# schematic.net
KiCad netlist of a schematic drawn in EAGLE
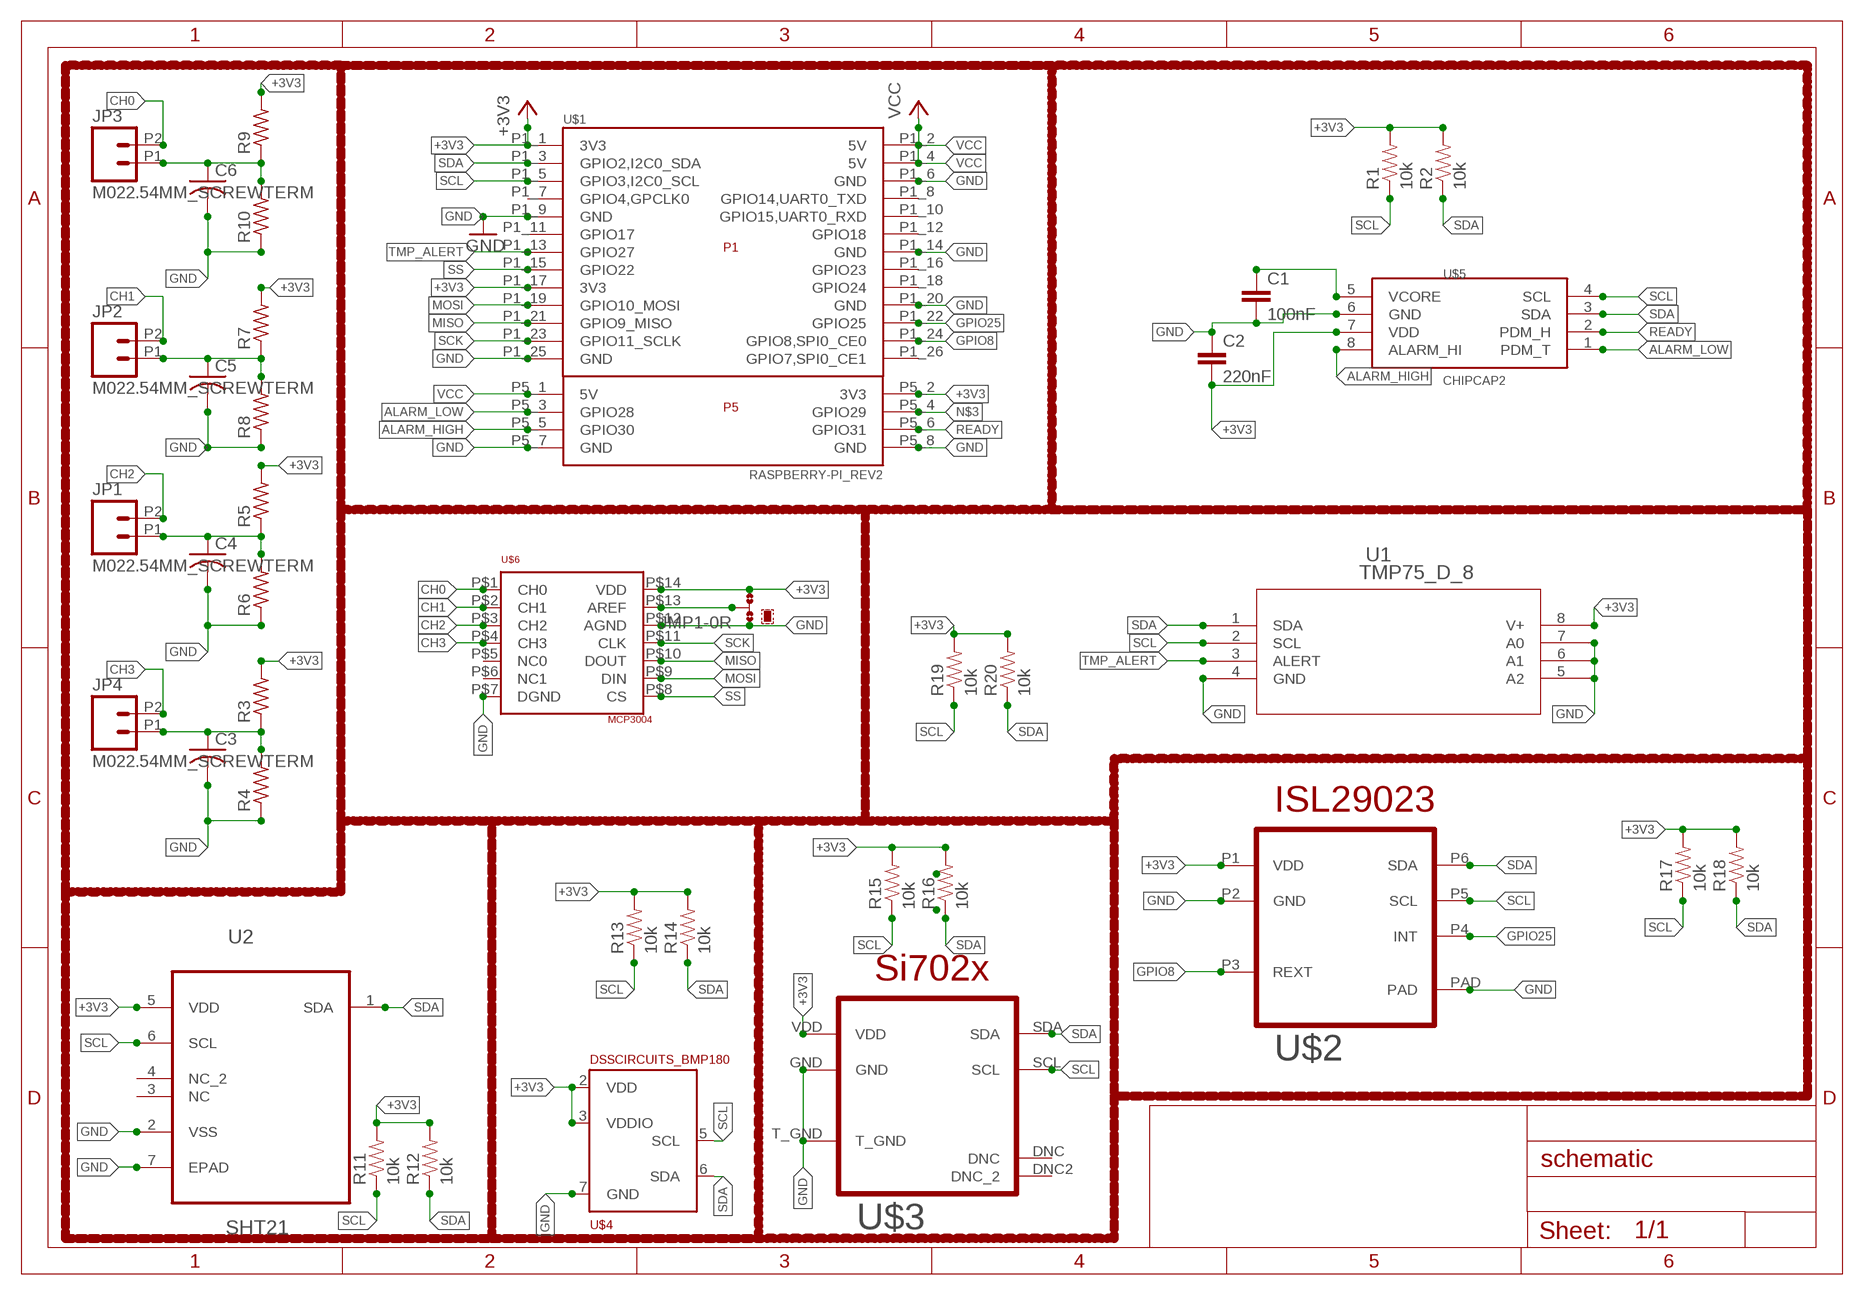
[diagram p0: schematic, sheet 1]

(export (version "E")
  (design (tool "Eeschema 10.0.6"))
  (components
    (comp (ref "C1")
      (value "100nF")
      (footprint "eagle-import:0402-CAP")
      (libsource (lib "eagle-import") (part "CAP0402-CAP"))
    )
    (comp (ref "C2")
      (value "220nF")
      (footprint "eagle-import:0402-CAP")
      (libsource (lib "eagle-import") (part "CAP0402-CAP"))
    )
    (comp (ref "C3")
      (value "C-USC0402")
      (footprint "eagle-import:C0402")
      (libsource (lib "eagle-import") (part "C-USC0402"))
    )
    (comp (ref "C4")
      (value "C-USC0402")
      (footprint "eagle-import:C0402")
      (libsource (lib "eagle-import") (part "C-USC0402"))
    )
    (comp (ref "C5")
      (value "C-USC0402")
      (footprint "eagle-import:C0402")
      (libsource (lib "eagle-import") (part "C-USC0402"))
    )
    (comp (ref "C6")
      (value "C-USC0402")
      (footprint "eagle-import:C0402")
      (libsource (lib "eagle-import") (part "C-USC0402"))
    )
    (comp (ref "JMP1")
      (value "0R-JUMPA")
      (footprint "eagle-import:A0R-JMP")
      (libsource (lib "eagle-import") (part "0R-JUMPA"))
    )
    (comp (ref "JP1")
      (value "M022.54MM_SCREWTERM")
      (footprint "eagle-import:1X02_2.54_SCREWTERM")
      (libsource (lib "eagle-import") (part "M022.54MM_SCREWTERM"))
    )
    (comp (ref "JP2")
      (value "M022.54MM_SCREWTERM")
      (footprint "eagle-import:1X02_2.54_SCREWTERM")
      (libsource (lib "eagle-import") (part "M022.54MM_SCREWTERM"))
    )
    (comp (ref "JP3")
      (value "M022.54MM_SCREWTERM")
      (footprint "eagle-import:1X02_2.54_SCREWTERM")
      (libsource (lib "eagle-import") (part "M022.54MM_SCREWTERM"))
    )
    (comp (ref "JP4")
      (value "M022.54MM_SCREWTERM")
      (footprint "eagle-import:1X02_2.54_SCREWTERM")
      (libsource (lib "eagle-import") (part "M022.54MM_SCREWTERM"))
    )
    (comp (ref "R1")
      (value "10k")
      (footprint "eagle-import:0603-RES")
      (libsource (lib "eagle-import") (part "RESISTOR0603"))
    )
    (comp (ref "R2")
      (value "10k")
      (footprint "eagle-import:0603-RES")
      (libsource (lib "eagle-import") (part "RESISTOR0603"))
    )
    (comp (ref "R3")
      (value "R-US_R0402")
      (footprint "eagle-import:R0402")
      (libsource (lib "eagle-import") (part "R-US_R0402"))
    )
    (comp (ref "R4")
      (value "R-US_R0402")
      (footprint "eagle-import:R0402")
      (libsource (lib "eagle-import") (part "R-US_R0402"))
    )
    (comp (ref "R5")
      (value "R-US_R0402")
      (footprint "eagle-import:R0402")
      (libsource (lib "eagle-import") (part "R-US_R0402"))
    )
    (comp (ref "R6")
      (value "R-US_R0402")
      (footprint "eagle-import:R0402")
      (libsource (lib "eagle-import") (part "R-US_R0402"))
    )
    (comp (ref "R7")
      (value "R-US_R0402")
      (footprint "eagle-import:R0402")
      (libsource (lib "eagle-import") (part "R-US_R0402"))
    )
    (comp (ref "R8")
      (value "R-US_R0402")
      (footprint "eagle-import:R0402")
      (libsource (lib "eagle-import") (part "R-US_R0402"))
    )
    (comp (ref "R9")
      (value "R-US_R0402")
      (footprint "eagle-import:R0402")
      (libsource (lib "eagle-import") (part "R-US_R0402"))
    )
    (comp (ref "R10")
      (value "R-US_R0402")
      (footprint "eagle-import:R0402")
      (libsource (lib "eagle-import") (part "R-US_R0402"))
    )
    (comp (ref "R11")
      (value "10k")
      (footprint "eagle-import:0603-RES")
      (libsource (lib "eagle-import") (part "RESISTOR0603"))
    )
    (comp (ref "R12")
      (value "10k")
      (footprint "eagle-import:0603-RES")
      (libsource (lib "eagle-import") (part "RESISTOR0603"))
    )
    (comp (ref "R13")
      (value "10k")
      (footprint "eagle-import:0603-RES")
      (libsource (lib "eagle-import") (part "RESISTOR0603"))
    )
    (comp (ref "R14")
      (value "10k")
      (footprint "eagle-import:0603-RES")
      (libsource (lib "eagle-import") (part "RESISTOR0603"))
    )
    (comp (ref "R15")
      (value "10k")
      (footprint "eagle-import:0603-RES")
      (libsource (lib "eagle-import") (part "RESISTOR0603"))
    )
    (comp (ref "R16")
      (value "10k")
      (footprint "eagle-import:0603-RES")
      (libsource (lib "eagle-import") (part "RESISTOR0603"))
    )
    (comp (ref "R17")
      (value "10k")
      (footprint "eagle-import:0603-RES")
      (libsource (lib "eagle-import") (part "RESISTOR0603"))
    )
    (comp (ref "R18")
      (value "10k")
      (footprint "eagle-import:0603-RES")
      (libsource (lib "eagle-import") (part "RESISTOR0603"))
    )
    (comp (ref "R19")
      (value "10k")
      (footprint "eagle-import:0603-RES")
      (libsource (lib "eagle-import") (part "RESISTOR0603"))
    )
    (comp (ref "R20")
      (value "10k")
      (footprint "eagle-import:0603-RES")
      (libsource (lib "eagle-import") (part "RESISTOR0603"))
    )
    (comp (ref "U$1")
      (value "RASPBERRY-PI_REV2")
      (footprint "eagle-import:RASPBERRY-PI_REV2")
      (libsource (lib "eagle-import") (part "RASPBERRY-PI_REV2"))
    )
    (comp (ref "U$2")
      (value "ISL29023")
      (footprint "eagle-import:ODFN6")
      (libsource (lib "eagle-import") (part "ISL29023"))
    )
    (comp (ref "U$3")
      (value "SI702X")
      (footprint "eagle-import:DFN6")
      (libsource (lib "eagle-import") (part "SI702X"))
    )
    (comp (ref "U$4")
      (value "DSSCIRCUITS_BMP180")
      (footprint "eagle-import:DSSCIRCUITS_LGA7")
      (libsource (lib "eagle-import") (part "DSSCIRCUITS_BMP180"))
    )
    (comp (ref "U$5")
      (value "CHIPCAP2")
      (footprint "eagle-import:CHIPCAP2")
      (libsource (lib "eagle-import") (part "CHIPCAP2"))
    )
    (comp (ref "U$6")
      (value "MCP3004")
      (footprint "eagle-import:TSSOP14_4MM4")
      (libsource (lib "eagle-import") (part "MCP3004"))
    )
    (comp (ref "U1")
      (value "TMP75_D_8")
      (footprint "eagle-import:D8")
      (fields
        (field (name "GENERIC_PART_NUMBER") "TMP75")
        (field (name "MANUFACTURER") "Texas Instruments")
        (field (name "MANUFACTURER_PART_NUMBER") "tmp75_d_8")
      )
      (libsource (lib "eagle-import") (part "TMP75_D_8"))
    )
    (comp (ref "U2")
      (value "SHT21")
      (footprint "eagle-import:DFN300X300X110-7N")
      (libsource (lib "eagle-import") (part "SHT21"))
    )
  )
  (nets
    (net (code "1") (name "+3V3") (class "Default")
      (node (ref "C2") (pin "2") (pinfunction "2_2") (pintype "passive"))
      (node (ref "JMP1") (pin "3") (pinfunction "3_3") (pintype "passive"))
      (node (ref "R1") (pin "2") (pinfunction "2_2") (pintype "passive"))
      (node (ref "R11") (pin "2") (pinfunction "2_2") (pintype "passive"))
      (node (ref "R12") (pin "2") (pinfunction "2_2") (pintype "passive"))
      (node (ref "R13") (pin "2") (pinfunction "2_2") (pintype "passive"))
      (node (ref "R14") (pin "2") (pinfunction "2_2") (pintype "passive"))
      (node (ref "R15") (pin "2") (pinfunction "2_2") (pintype "passive"))
      (node (ref "R16") (pin "2") (pinfunction "2_2") (pintype "passive"))
      (node (ref "R17") (pin "2") (pinfunction "2_2") (pintype "passive"))
      (node (ref "R18") (pin "2") (pinfunction "2_2") (pintype "passive"))
      (node (ref "R19") (pin "2") (pinfunction "2_2") (pintype "passive"))
      (node (ref "R2") (pin "2") (pinfunction "2_2") (pintype "passive"))
      (node (ref "R20") (pin "2") (pinfunction "2_2") (pintype "passive"))
      (node (ref "R3") (pin "2") (pinfunction "2_2") (pintype "passive"))
      (node (ref "R5") (pin "2") (pinfunction "2_2") (pintype "passive"))
      (node (ref "R7") (pin "2") (pinfunction "2_2") (pintype "passive"))
      (node (ref "R9") (pin "2") (pinfunction "2_2") (pintype "passive"))
      (node (ref "U$1") (pin "P1_1") (pinfunction "3V3_P1_1") (pintype "bidirectional"))
      (node (ref "U$1") (pin "P1_17") (pinfunction "3V3_P1_17") (pintype "bidirectional"))
      (node (ref "U$1") (pin "P5_2") (pinfunction "3V3_P5_2") (pintype "bidirectional"))
      (node (ref "U$2") (pin "P1") (pinfunction "VDD_P1") (pintype "bidirectional"))
      (node (ref "U$3") (pin "VDD") (pinfunction "VDD_VDD") (pintype "bidirectional"))
      (node (ref "U$4") (pin "2") (pinfunction "VDD_2") (pintype "power_in"))
      (node (ref "U$4") (pin "3") (pinfunction "VDDIO_3") (pintype "power_in"))
      (node (ref "U$5") (pin "7") (pinfunction "VDD_7") (pintype "bidirectional"))
      (node (ref "U$6") (pin "P$14") (pinfunction "VDD_P$14") (pintype "bidirectional"))
      (node (ref "U1") (pin "8") (pinfunction "V+_8") (pintype "power_in"))
      (node (ref "U2") (pin "5") (pinfunction "VDD_5") (pintype "power_in"))
    )
    (net (code "2") (name "ALARM_HIGH") (class "Default")
      (node (ref "U$1") (pin "P5_5") (pinfunction "GPIO30_P5_5") (pintype "bidirectional"))
      (node (ref "U$5") (pin "8") (pinfunction "ALARM_HI_8") (pintype "bidirectional"))
    )
    (net (code "3") (name "ALARM_LOW") (class "Default")
      (node (ref "U$1") (pin "P5_3") (pinfunction "GPIO28_P5_3") (pintype "bidirectional"))
      (node (ref "U$5") (pin "1") (pinfunction "PDM_T_1") (pintype "bidirectional"))
    )
    (net (code "4") (name "CH0") (class "Default")
      (node (ref "JP3") (pin "P2") (pinfunction "2_P2") (pintype "passive"))
      (node (ref "U$6") (pin "P$1") (pinfunction "CH0_P$1") (pintype "bidirectional"))
    )
    (net (code "5") (name "CH1") (class "Default")
      (node (ref "JP2") (pin "P2") (pinfunction "2_P2") (pintype "passive"))
      (node (ref "U$6") (pin "P$2") (pinfunction "CH1_P$2") (pintype "bidirectional"))
    )
    (net (code "6") (name "CH2") (class "Default")
      (node (ref "JP1") (pin "P2") (pinfunction "2_P2") (pintype "passive"))
      (node (ref "U$6") (pin "P$3") (pinfunction "CH2_P$3") (pintype "bidirectional"))
    )
    (net (code "7") (name "CH3") (class "Default")
      (node (ref "JP4") (pin "P2") (pinfunction "2_P2") (pintype "passive"))
      (node (ref "U$6") (pin "P$4") (pinfunction "CH3_P$4") (pintype "bidirectional"))
    )
    (net (code "8") (name "GND") (class "Default")
      (node (ref "C1") (pin "2") (pinfunction "2_2") (pintype "passive"))
      (node (ref "C2") (pin "1") (pinfunction "1_1") (pintype "passive"))
      (node (ref "C3") (pin "2") (pinfunction "2_2") (pintype "passive"))
      (node (ref "C4") (pin "2") (pinfunction "2_2") (pintype "passive"))
      (node (ref "C5") (pin "2") (pinfunction "2_2") (pintype "passive"))
      (node (ref "C6") (pin "2") (pinfunction "2_2") (pintype "passive"))
      (node (ref "JMP1") (pin "1") (pinfunction "1_1") (pintype "passive"))
      (node (ref "R10") (pin "1") (pinfunction "1_1") (pintype "passive"))
      (node (ref "R4") (pin "1") (pinfunction "1_1") (pintype "passive"))
      (node (ref "R6") (pin "1") (pinfunction "1_1") (pintype "passive"))
      (node (ref "R8") (pin "1") (pinfunction "1_1") (pintype "passive"))
      (node (ref "U$1") (pin "P1_14") (pinfunction "GND_P1_14") (pintype "bidirectional"))
      (node (ref "U$1") (pin "P1_20") (pinfunction "GND_P1_20") (pintype "bidirectional"))
      (node (ref "U$1") (pin "P1_25") (pinfunction "GND_P1_25") (pintype "bidirectional"))
      (node (ref "U$1") (pin "P1_6") (pinfunction "GND_P1_6") (pintype "bidirectional"))
      (node (ref "U$1") (pin "P1_9") (pinfunction "GND_P1_9") (pintype "bidirectional"))
      (node (ref "U$1") (pin "P5_7") (pinfunction "GND_P5_7") (pintype "bidirectional"))
      (node (ref "U$1") (pin "P5_8") (pinfunction "GND_P5_8") (pintype "bidirectional"))
      (node (ref "U$2") (pin "P2") (pinfunction "GND_P2") (pintype "bidirectional"))
      (node (ref "U$2") (pin "PAD") (pinfunction "PAD_PAD") (pintype "bidirectional"))
      (node (ref "U$3") (pin "GND") (pinfunction "GND_GND") (pintype "bidirectional"))
      (node (ref "U$3") (pin "T_GND") (pinfunction "T_GND_T_GND") (pintype "bidirectional"))
      (node (ref "U$4") (pin "7") (pinfunction "GND_7") (pintype "power_in"))
      (node (ref "U$5") (pin "6") (pinfunction "GND_6") (pintype "bidirectional"))
      (node (ref "U$6") (pin "P$12") (pinfunction "AGND_P$12") (pintype "bidirectional"))
      (node (ref "U$6") (pin "P$7") (pinfunction "DGND_P$7") (pintype "bidirectional"))
      (node (ref "U1") (pin "4") (pinfunction "GND_4") (pintype "power_in"))
      (node (ref "U1") (pin "5") (pinfunction "A2_5") (pintype "passive"))
      (node (ref "U1") (pin "6") (pinfunction "A1_6") (pintype "passive"))
      (node (ref "U1") (pin "7") (pinfunction "A0_7") (pintype "passive"))
      (node (ref "U2") (pin "2") (pinfunction "VSS_2") (pintype "power_in"))
      (node (ref "U2") (pin "7") (pinfunction "EPAD_7") (pintype "passive"))
    )
    (net (code "9") (name "GPIO8") (class "Default")
      (node (ref "U$1") (pin "P1_24") (pinfunction "GPIO8,SPI0_CE0_P1_24") (pintype "bidirectional"))
      (node (ref "U$2") (pin "P3") (pinfunction "REXT_P3") (pintype "bidirectional"))
    )
    (net (code "10") (name "GPIO25") (class "Default")
      (node (ref "U$1") (pin "P1_22") (pinfunction "GPIO25_P1_22") (pintype "bidirectional"))
      (node (ref "U$2") (pin "P4") (pinfunction "INT_P4") (pintype "bidirectional"))
    )
    (net (code "11") (name "MISO") (class "Default")
      (node (ref "U$1") (pin "P1_21") (pinfunction "GPIO9_MISO_P1_21") (pintype "bidirectional"))
      (node (ref "U$6") (pin "P$10") (pinfunction "DOUT_P$10") (pintype "bidirectional"))
    )
    (net (code "12") (name "MOSI") (class "Default")
      (node (ref "U$1") (pin "P1_19") (pinfunction "GPIO10_MOSI_P1_19") (pintype "bidirectional"))
      (node (ref "U$6") (pin "P$9") (pinfunction "DIN_P$9") (pintype "bidirectional"))
    )
    (net (code "13") (name "N$3") (class "Default")
      (node (ref "U$1") (pin "P5_4") (pinfunction "GPIO29_P5_4") (pintype "bidirectional"))
    )
    (net (code "14") (name "Net-(JP1-1)") (class "Default")
      (node (ref "C4") (pin "1") (pinfunction "1_1") (pintype "passive"))
      (node (ref "JP1") (pin "P1") (pinfunction "1_P1") (pintype "passive"))
      (node (ref "R5") (pin "1") (pinfunction "1_1") (pintype "passive"))
      (node (ref "R6") (pin "2") (pinfunction "2_2") (pintype "passive"))
    )
    (net (code "15") (name "Net-(JP2-1)") (class "Default")
      (node (ref "C5") (pin "1") (pinfunction "1_1") (pintype "passive"))
      (node (ref "JP2") (pin "P1") (pinfunction "1_P1") (pintype "passive"))
      (node (ref "R7") (pin "1") (pinfunction "1_1") (pintype "passive"))
      (node (ref "R8") (pin "2") (pinfunction "2_2") (pintype "passive"))
    )
    (net (code "16") (name "Net-(JP3-1)") (class "Default")
      (node (ref "C6") (pin "1") (pinfunction "1_1") (pintype "passive"))
      (node (ref "JP3") (pin "P1") (pinfunction "1_P1") (pintype "passive"))
      (node (ref "R10") (pin "2") (pinfunction "2_2") (pintype "passive"))
      (node (ref "R9") (pin "1") (pinfunction "1_1") (pintype "passive"))
    )
    (net (code "17") (name "Net-(JP4-1)") (class "Default")
      (node (ref "C3") (pin "1") (pinfunction "1_1") (pintype "passive"))
      (node (ref "JP4") (pin "P1") (pinfunction "1_P1") (pintype "passive"))
      (node (ref "R3") (pin "1") (pinfunction "1_1") (pintype "passive"))
      (node (ref "R4") (pin "2") (pinfunction "2_2") (pintype "passive"))
    )
    (net (code "18") (name "Net-(U$5-VCORE)") (class "Default")
      (node (ref "C1") (pin "1") (pinfunction "1_1") (pintype "passive"))
      (node (ref "U$5") (pin "5") (pinfunction "VCORE_5") (pintype "bidirectional"))
    )
    (net (code "19") (name "Net-(U$6-AREF)") (class "Default")
      (node (ref "JMP1") (pin "2") (pinfunction "2_2") (pintype "passive"))
      (node (ref "U$6") (pin "P$13") (pinfunction "AREF_P$13") (pintype "bidirectional"))
    )
    (net (code "20") (name "READY") (class "Default")
      (node (ref "U$1") (pin "P5_6") (pinfunction "GPIO31_P5_6") (pintype "bidirectional"))
      (node (ref "U$5") (pin "2") (pinfunction "PDM_H_2") (pintype "bidirectional"))
    )
    (net (code "21") (name "SCK") (class "Default")
      (node (ref "U$1") (pin "P1_23") (pinfunction "GPIO11_SCLK_P1_23") (pintype "bidirectional"))
      (node (ref "U$6") (pin "P$11") (pinfunction "CLK_P$11") (pintype "bidirectional"))
    )
    (net (code "22") (name "SCL") (class "Default")
      (node (ref "R1") (pin "1") (pinfunction "1_1") (pintype "passive"))
      (node (ref "R11") (pin "1") (pinfunction "1_1") (pintype "passive"))
      (node (ref "R13") (pin "1") (pinfunction "1_1") (pintype "passive"))
      (node (ref "R15") (pin "1") (pinfunction "1_1") (pintype "passive"))
      (node (ref "R17") (pin "1") (pinfunction "1_1") (pintype "passive"))
      (node (ref "R19") (pin "1") (pinfunction "1_1") (pintype "passive"))
      (node (ref "U$1") (pin "P1_5") (pinfunction "GPIO3,I2C0_SCL_P1_5") (pintype "bidirectional"))
      (node (ref "U$2") (pin "P5") (pinfunction "SCL_P5") (pintype "bidirectional"))
      (node (ref "U$3") (pin "SCL") (pinfunction "SCL_SCL") (pintype "bidirectional"))
      (node (ref "U$4") (pin "5") (pinfunction "SCL_5") (pintype "bidirectional"))
      (node (ref "U$5") (pin "4") (pinfunction "SCL_4") (pintype "bidirectional"))
      (node (ref "U1") (pin "2") (pinfunction "SCL_2") (pintype "passive"))
      (node (ref "U2") (pin "6") (pinfunction "SCL_6") (pintype "input"))
    )
    (net (code "23") (name "SDA") (class "Default")
      (node (ref "R12") (pin "1") (pinfunction "1_1") (pintype "passive"))
      (node (ref "R14") (pin "1") (pinfunction "1_1") (pintype "passive"))
      (node (ref "R16") (pin "1") (pinfunction "1_1") (pintype "passive"))
      (node (ref "R18") (pin "1") (pinfunction "1_1") (pintype "passive"))
      (node (ref "R2") (pin "1") (pinfunction "1_1") (pintype "passive"))
      (node (ref "R20") (pin "1") (pinfunction "1_1") (pintype "passive"))
      (node (ref "U$1") (pin "P1_3") (pinfunction "GPIO2,I2C0_SDA_P1_3") (pintype "bidirectional"))
      (node (ref "U$2") (pin "P6") (pinfunction "SDA_P6") (pintype "bidirectional"))
      (node (ref "U$3") (pin "SDA") (pinfunction "SDA_SDA") (pintype "bidirectional"))
      (node (ref "U$4") (pin "6") (pinfunction "SDA_6") (pintype "bidirectional"))
      (node (ref "U$5") (pin "3") (pinfunction "SDA_3") (pintype "bidirectional"))
      (node (ref "U1") (pin "1") (pinfunction "SDA_1") (pintype "passive"))
      (node (ref "U2") (pin "1") (pinfunction "SDA_1") (pintype "bidirectional"))
    )
    (net (code "24") (name "SS") (class "Default")
      (node (ref "U$1") (pin "P1_15") (pinfunction "GPIO22_P1_15") (pintype "bidirectional"))
      (node (ref "U$6") (pin "P$8") (pinfunction "CS_P$8") (pintype "bidirectional"))
    )
    (net (code "25") (name "TMP_ALERT") (class "Default")
      (node (ref "U$1") (pin "P1_13") (pinfunction "GPIO27_P1_13") (pintype "bidirectional"))
      (node (ref "U1") (pin "3") (pinfunction "ALERT_3") (pintype "passive"))
    )
    (net (code "26") (name "VCC") (class "Default")
      (node (ref "U$1") (pin "P1_2") (pinfunction "5V_P1_2") (pintype "bidirectional"))
      (node (ref "U$1") (pin "P1_4") (pinfunction "5V_P1_4") (pintype "bidirectional"))
      (node (ref "U$1") (pin "P5_1") (pinfunction "5V_P5_1") (pintype "bidirectional"))
    )
    (net (code "27") (name "unconnected-(U$1-GPIO4,GPCLK0-PadP1_7)") (class "Default")
      (node (ref "U$1") (pin "P1_7") (pinfunction "GPIO4,GPCLK0_P1_7") (pintype "bidirectional"))
    )
    (net (code "28") (name "unconnected-(U$1-GPIO7,SPI0_CE1-PadP1_26)") (class "Default")
      (node (ref "U$1") (pin "P1_26") (pinfunction "GPIO7,SPI0_CE1_P1_26") (pintype "bidirectional"))
    )
    (net (code "29") (name "unconnected-(U$1-GPIO14,UART0_TXD-PadP1_8)") (class "Default")
      (node (ref "U$1") (pin "P1_8") (pinfunction "GPIO14,UART0_TXD_P1_8") (pintype "bidirectional"))
    )
    (net (code "30") (name "unconnected-(U$1-GPIO15,UART0_RXD-PadP1_10)") (class "Default")
      (node (ref "U$1") (pin "P1_10") (pinfunction "GPIO15,UART0_RXD_P1_10") (pintype "bidirectional"))
    )
    (net (code "31") (name "unconnected-(U$1-GPIO17-PadP1_11)") (class "Default")
      (node (ref "U$1") (pin "P1_11") (pinfunction "GPIO17_P1_11") (pintype "bidirectional"))
    )
    (net (code "32") (name "unconnected-(U$1-GPIO18-PadP1_12)") (class "Default")
      (node (ref "U$1") (pin "P1_12") (pinfunction "GPIO18_P1_12") (pintype "bidirectional"))
    )
    (net (code "33") (name "unconnected-(U$1-GPIO23-PadP1_16)") (class "Default")
      (node (ref "U$1") (pin "P1_16") (pinfunction "GPIO23_P1_16") (pintype "bidirectional"))
    )
    (net (code "34") (name "unconnected-(U$1-GPIO24-PadP1_18)") (class "Default")
      (node (ref "U$1") (pin "P1_18") (pinfunction "GPIO24_P1_18") (pintype "bidirectional"))
    )
    (net (code "35") (name "unconnected-(U$3-DNC_2-PadDNC2)") (class "Default")
      (node (ref "U$3") (pin "DNC2") (pinfunction "DNC_2_DNC2") (pintype "bidirectional"))
    )
    (net (code "36") (name "unconnected-(U$3-PadDNC)") (class "Default")
      (node (ref "U$3") (pin "DNC") (pinfunction "DNC_DNC") (pintype "bidirectional"))
    )
    (net (code "37") (name "unconnected-(U$4-P$1-Pad1)") (class "Default")
      (node (ref "U$4") (pin "1") (pinfunction "P$1_1") (pintype "no_connect"))
    )
    (net (code "38") (name "unconnected-(U$4-P$2-Pad4)") (class "Default")
      (node (ref "U$4") (pin "4") (pinfunction "P$2_4") (pintype "no_connect"))
    )
    (net (code "39") (name "unconnected-(U$6-NC0-PadP$5)") (class "Default")
      (node (ref "U$6") (pin "P$5") (pinfunction "NC0_P$5") (pintype "no_connect"))
    )
    (net (code "40") (name "unconnected-(U$6-NC1-PadP$6)") (class "Default")
      (node (ref "U$6") (pin "P$6") (pinfunction "NC1_P$6") (pintype "no_connect"))
    )
    (net (code "41") (name "unconnected-(U2-NC-Pad3)") (class "Default")
      (node (ref "U2") (pin "3") (pinfunction "NC_3") (pintype "no_connect"))
    )
    (net (code "42") (name "unconnected-(U2-NC_2-Pad4)") (class "Default")
      (node (ref "U2") (pin "4") (pinfunction "NC_2_4") (pintype "no_connect"))
    )
  )
)
